# DC075B_JESD_OUTPUT.net
KiCad netlist of a schematic drawn in Altium Designer
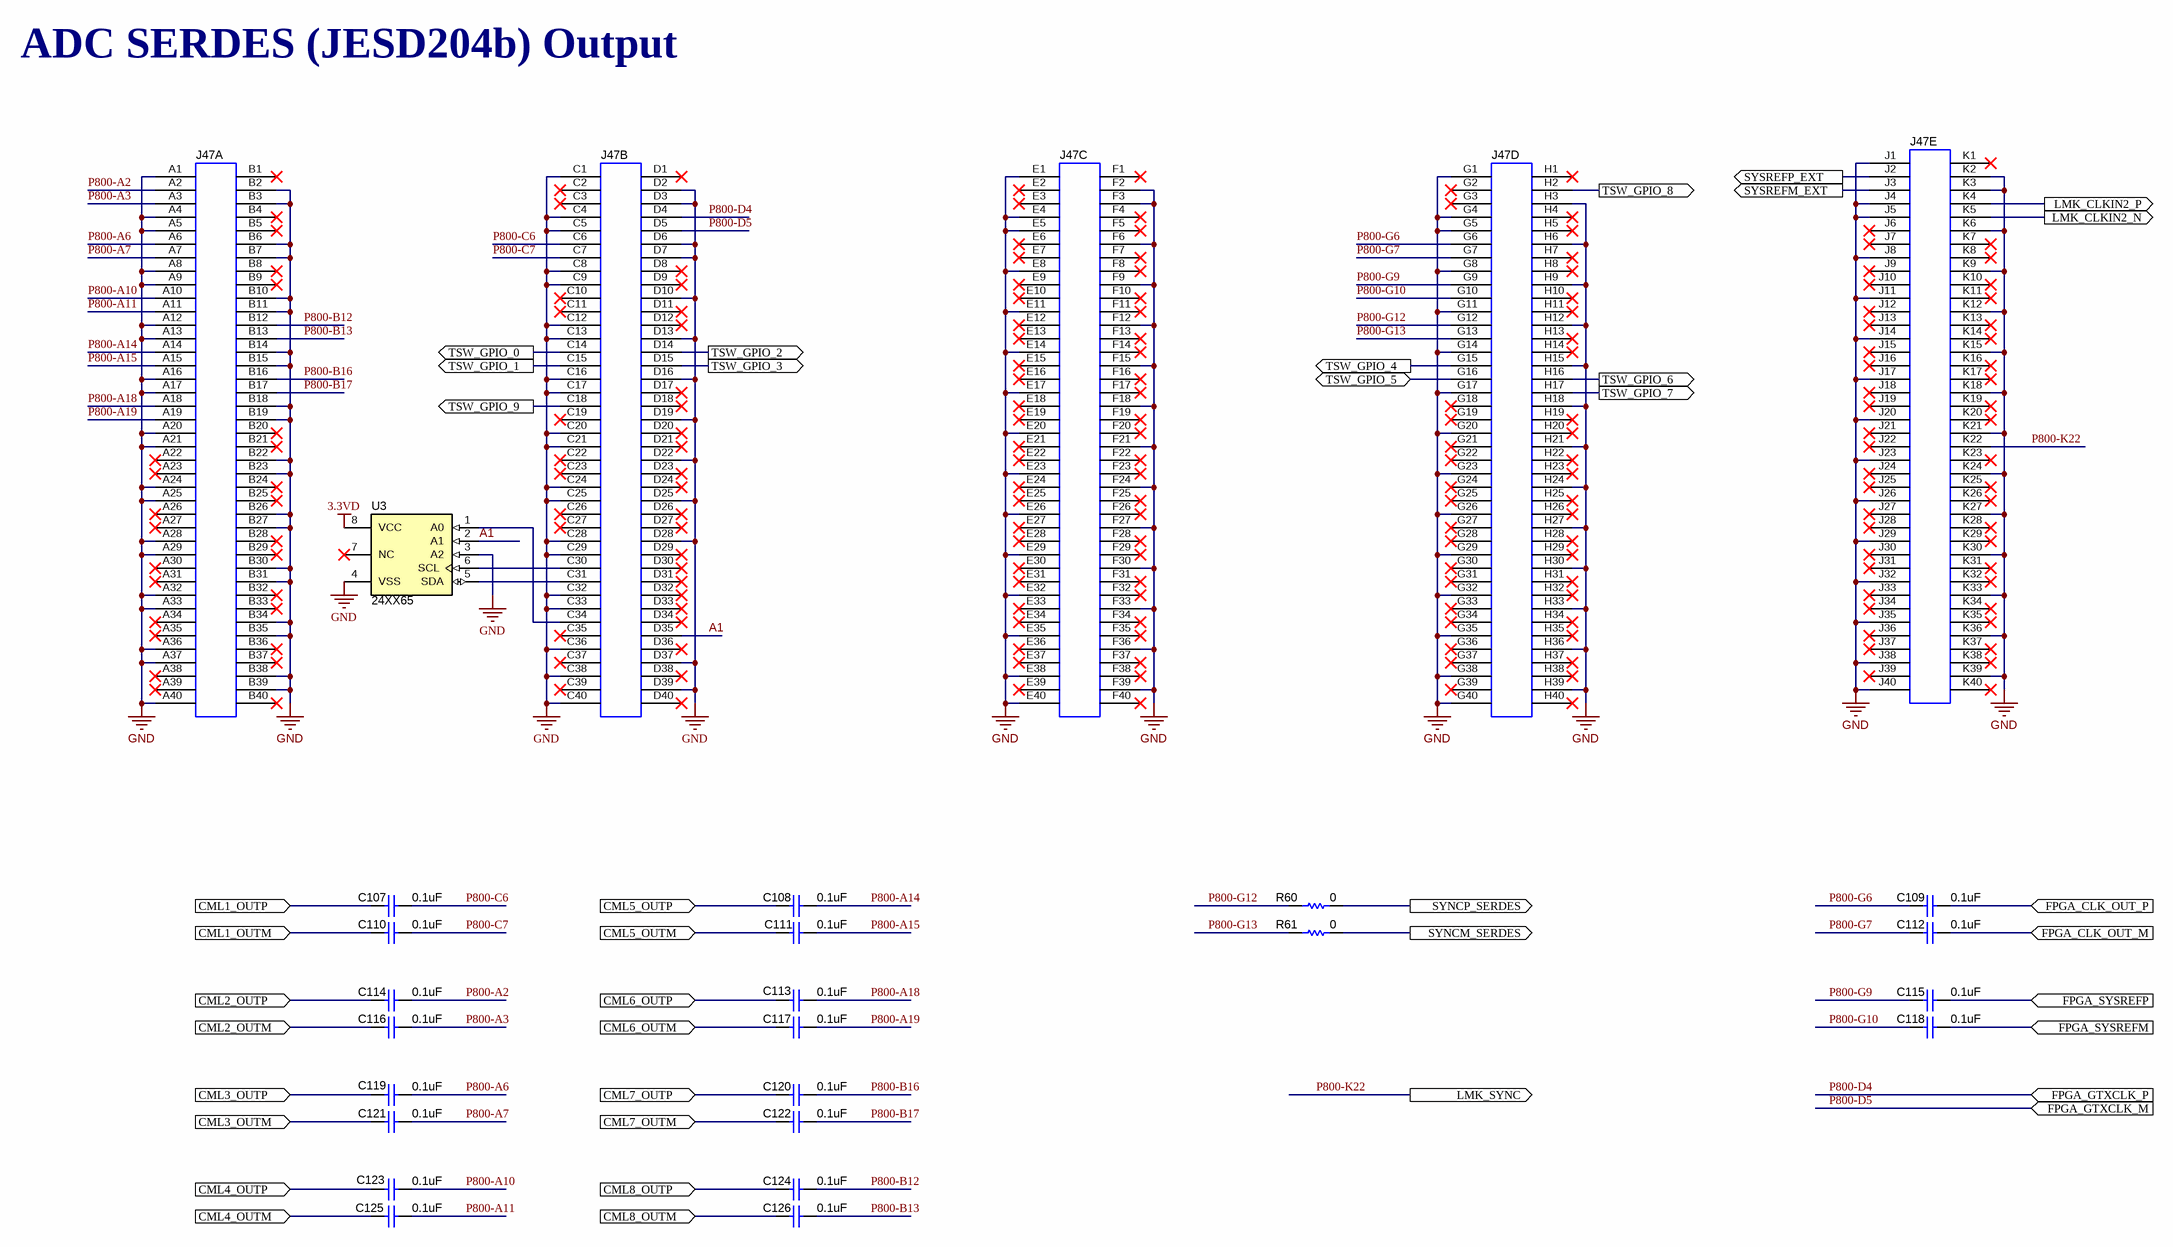
[diagram p0: DC075B_JESD_OUTPUT.SchDoc]

(export (version "E")
  (design (tool "Eeschema 10.0.6"))
  (components
    (comp (ref "C107")
      (value "0.1uF")
      (footprint "0402")
      (description "CAP, CERM, 0.1 uF, 16 V, +/- 10%, X7R, 0402")
      (fields
        (field (name "PARTNUMBER") "GRM155R71C104KA88D")
        (field (name "MANUFACTURER") "MuRata")
        (field (name "PUBLISHER") "Texas Instruments")
      )
      (libsource (lib "Altium Vault - TI") (part "Capacitor"))
    )
    (comp (ref "C108")
      (value "0.1uF")
      (footprint "0402")
      (description "CAP, CERM, 0.1 uF, 16 V, +/- 10%, X7R, 0402")
      (fields
        (field (name "PARTNUMBER") "GRM155R71C104KA88D")
        (field (name "MANUFACTURER") "MuRata")
        (field (name "PUBLISHER") "Texas Instruments")
      )
      (libsource (lib "Altium Vault - TI") (part "Capacitor"))
    )
    (comp (ref "C109")
      (value "0.1uF")
      (footprint "0402")
      (description "CAP, CERM, 0.1 uF, 16 V, +/- 10%, X7R, 0402")
      (fields
        (field (name "PARTNUMBER") "GRM155R71C104KA88D")
        (field (name "MANUFACTURER") "MuRata")
        (field (name "PUBLISHER") "Texas Instruments")
      )
      (libsource (lib "Altium Vault - TI") (part "Capacitor"))
    )
    (comp (ref "C110")
      (value "0.1uF")
      (footprint "0402")
      (description "CAP, CERM, 0.1 uF, 16 V, +/- 10%, X7R, 0402")
      (fields
        (field (name "PARTNUMBER") "GRM155R71C104KA88D")
        (field (name "MANUFACTURER") "MuRata")
        (field (name "PUBLISHER") "Texas Instruments")
      )
      (libsource (lib "Altium Vault - TI") (part "Capacitor"))
    )
    (comp (ref "C111")
      (value "0.1uF")
      (footprint "0402")
      (description "CAP, CERM, 0.1 uF, 16 V, +/- 10%, X7R, 0402")
      (fields
        (field (name "PARTNUMBER") "GRM155R71C104KA88D")
        (field (name "MANUFACTURER") "MuRata")
        (field (name "PUBLISHER") "Texas Instruments")
      )
      (libsource (lib "Altium Vault - TI") (part "Capacitor"))
    )
    (comp (ref "C112")
      (value "0.1uF")
      (footprint "0402")
      (description "CAP, CERM, 0.1 uF, 16 V, +/- 10%, X7R, 0402")
      (fields
        (field (name "PARTNUMBER") "GRM155R71C104KA88D")
        (field (name "MANUFACTURER") "MuRata")
        (field (name "PUBLISHER") "Texas Instruments")
      )
      (libsource (lib "Altium Vault - TI") (part "Capacitor"))
    )
    (comp (ref "C113")
      (value "0.1uF")
      (footprint "0402")
      (description "CAP, CERM, 0.1 uF, 16 V, +/- 10%, X7R, 0402")
      (fields
        (field (name "PARTNUMBER") "GRM155R71C104KA88D")
        (field (name "MANUFACTURER") "MuRata")
        (field (name "PUBLISHER") "Texas Instruments")
      )
      (libsource (lib "Altium Vault - TI") (part "Capacitor"))
    )
    (comp (ref "C114")
      (value "0.1uF")
      (footprint "0402")
      (description "CAP, CERM, 0.1 uF, 16 V, +/- 10%, X7R, 0402")
      (fields
        (field (name "PARTNUMBER") "GRM155R71C104KA88D")
        (field (name "MANUFACTURER") "MuRata")
        (field (name "PUBLISHER") "Texas Instruments")
      )
      (libsource (lib "Altium Vault - TI") (part "Capacitor"))
    )
    (comp (ref "C115")
      (value "0.1uF")
      (footprint "0402")
      (description "CAP, CERM, 0.1 uF, 16 V, +/- 10%, X7R, 0402")
      (fields
        (field (name "PARTNUMBER") "GRM155R71C104KA88D")
        (field (name "MANUFACTURER") "MuRata")
        (field (name "PUBLISHER") "Texas Instruments")
      )
      (libsource (lib "Altium Vault - TI") (part "Capacitor"))
    )
    (comp (ref "C116")
      (value "0.1uF")
      (footprint "0402")
      (description "CAP, CERM, 0.1 uF, 16 V, +/- 10%, X7R, 0402")
      (fields
        (field (name "PARTNUMBER") "GRM155R71C104KA88D")
        (field (name "MANUFACTURER") "MuRata")
        (field (name "PUBLISHER") "Texas Instruments")
      )
      (libsource (lib "Altium Vault - TI") (part "Capacitor"))
    )
    (comp (ref "C117")
      (value "0.1uF")
      (footprint "0402")
      (description "CAP, CERM, 0.1 uF, 16 V, +/- 10%, X7R, 0402")
      (fields
        (field (name "PARTNUMBER") "GRM155R71C104KA88D")
        (field (name "MANUFACTURER") "MuRata")
        (field (name "PUBLISHER") "Texas Instruments")
      )
      (libsource (lib "Altium Vault - TI") (part "Capacitor"))
    )
    (comp (ref "C118")
      (value "0.1uF")
      (footprint "0402")
      (description "CAP, CERM, 0.1 uF, 16 V, +/- 10%, X7R, 0402")
      (fields
        (field (name "PARTNUMBER") "GRM155R71C104KA88D")
        (field (name "MANUFACTURER") "MuRata")
        (field (name "PUBLISHER") "Texas Instruments")
      )
      (libsource (lib "Altium Vault - TI") (part "Capacitor"))
    )
    (comp (ref "C119")
      (value "0.1uF")
      (footprint "0402")
      (description "CAP, CERM, 0.1 uF, 16 V, +/- 10%, X7R, 0402")
      (fields
        (field (name "PARTNUMBER") "GRM155R71C104KA88D")
        (field (name "MANUFACTURER") "MuRata")
        (field (name "PUBLISHER") "Texas Instruments")
      )
      (libsource (lib "Altium Vault - TI") (part "Capacitor"))
    )
    (comp (ref "C120")
      (value "0.1uF")
      (footprint "0402")
      (description "CAP, CERM, 0.1 uF, 16 V, +/- 10%, X7R, 0402")
      (fields
        (field (name "PARTNUMBER") "GRM155R71C104KA88D")
        (field (name "MANUFACTURER") "MuRata")
        (field (name "PUBLISHER") "Texas Instruments")
      )
      (libsource (lib "Altium Vault - TI") (part "Capacitor"))
    )
    (comp (ref "C121")
      (value "0.1uF")
      (footprint "0402")
      (description "CAP, CERM, 0.1 uF, 16 V, +/- 10%, X7R, 0402")
      (fields
        (field (name "PARTNUMBER") "GRM155R71C104KA88D")
        (field (name "MANUFACTURER") "MuRata")
        (field (name "PUBLISHER") "Texas Instruments")
      )
      (libsource (lib "Altium Vault - TI") (part "Capacitor"))
    )
    (comp (ref "C122")
      (value "0.1uF")
      (footprint "0402")
      (description "CAP, CERM, 0.1 uF, 16 V, +/- 10%, X7R, 0402")
      (fields
        (field (name "PARTNUMBER") "GRM155R71C104KA88D")
        (field (name "MANUFACTURER") "MuRata")
        (field (name "PUBLISHER") "Texas Instruments")
      )
      (libsource (lib "Altium Vault - TI") (part "Capacitor"))
    )
    (comp (ref "C123")
      (value "0.1uF")
      (footprint "0402")
      (description "CAP, CERM, 0.1 uF, 16 V, +/- 10%, X7R, 0402")
      (fields
        (field (name "PARTNUMBER") "GRM155R71C104KA88D")
        (field (name "MANUFACTURER") "MuRata")
        (field (name "PUBLISHER") "Texas Instruments")
      )
      (libsource (lib "Altium Vault - TI") (part "Capacitor"))
    )
    (comp (ref "C124")
      (value "0.1uF")
      (footprint "0402")
      (description "CAP, CERM, 0.1 uF, 16 V, +/- 10%, X7R, 0402")
      (fields
        (field (name "PARTNUMBER") "GRM155R71C104KA88D")
        (field (name "MANUFACTURER") "MuRata")
        (field (name "PUBLISHER") "Texas Instruments")
      )
      (libsource (lib "Altium Vault - TI") (part "Capacitor"))
    )
    (comp (ref "C125")
      (value "0.1uF")
      (footprint "0402")
      (description "CAP, CERM, 0.1 uF, 16 V, +/- 10%, X7R, 0402")
      (fields
        (field (name "PARTNUMBER") "GRM155R71C104KA88D")
        (field (name "MANUFACTURER") "MuRata")
        (field (name "PUBLISHER") "Texas Instruments")
      )
      (libsource (lib "Altium Vault - TI") (part "Capacitor"))
    )
    (comp (ref "C126")
      (value "0.1uF")
      (footprint "0402")
      (description "CAP, CERM, 0.1 uF, 16 V, +/- 10%, X7R, 0402")
      (fields
        (field (name "PARTNUMBER") "GRM155R71C104KA88D")
        (field (name "MANUFACTURER") "MuRata")
        (field (name "PUBLISHER") "Texas Instruments")
      )
      (libsource (lib "Altium Vault - TI") (part "Capacitor"))
    )
    (comp (ref "J47")
      (value "SAMTEC_ASP-134602-01")
      (footprint "SAMTEC_ASP-134602-01")
      (description "Connector, Male, 1.27 mm, 40x4, SMD")
      (fields
        (field (name "PARTNUMBER") "ASP-134602-01")
        (field (name "MANUFACTURER") "Samtec")
        (field (name "PUBLISHER") "Texas Instruments")
      )
      (libsource (lib "Altium Vault - TI") (part "SAMTEC_ASP-134602-01"))
    )
    (comp (ref "R60")
      (value "0")
      (footprint "0402")
      (description "RES, 0, 5%, 0.063 W, AEC-Q200 Grade 0, 0402")
      (fields (field (name "MANUFACTURER") "Vishay-Dale") (field (name "PARTNUMBER") "CRCW04020000Z0ED"))
      (libsource (lib "Altium Vault - TI") (part "Resistor"))
    )
    (comp (ref "R61")
      (value "0")
      (footprint "0402")
      (description "RES, 0, 5%, 0.063 W, AEC-Q200 Grade 0, 0402")
      (fields (field (name "MANUFACTURER") "Vishay-Dale") (field (name "PARTNUMBER") "CRCW04020000Z0ED"))
      (libsource (lib "Altium Vault - TI") (part "Resistor"))
    )
    (comp (ref "U3")
      (value "24XX65")
      (footprint "SOIC127P800X216-8N")
      (description "64K I2C Smart Serial EEPROM, SOIC-8")
      (fields
        (field (name "PARTNUMBER") "24LC65-I/SM")
        (field (name "MANUFACTURER") "Microchip")
        (field (name "PUBLISHER") "Texas Instruments")
      )
      (libsource (lib "Altium Vault - TI") (part "24XX65"))
    )
  )
  (nets
    (net (code "1") (name "/A1") (class "Default")
      (node (ref "J47") (pin "D35") (pintype "passive"))
      (node (ref "U3") (pin "2") (pinfunction "A1_2") (pintype "input"))
    )
    (net (code "2") (name "/CML1_OUTM") (class "Default")
      (node (ref "C110") (pin "2") (pinfunction "2_2") (pintype "passive"))
    )
    (net (code "3") (name "/CML1_OUTP") (class "Default")
      (node (ref "C107") (pin "2") (pinfunction "2_2") (pintype "passive"))
    )
    (net (code "4") (name "/CML2_OUTM") (class "Default")
      (node (ref "C116") (pin "2") (pinfunction "2_2") (pintype "passive"))
    )
    (net (code "5") (name "/CML2_OUTP") (class "Default")
      (node (ref "C114") (pin "2") (pinfunction "2_2") (pintype "passive"))
    )
    (net (code "6") (name "/CML3_OUTM") (class "Default")
      (node (ref "C121") (pin "2") (pinfunction "2_2") (pintype "passive"))
    )
    (net (code "7") (name "/CML3_OUTP") (class "Default")
      (node (ref "C119") (pin "2") (pinfunction "2_2") (pintype "passive"))
    )
    (net (code "8") (name "/CML4_OUTM") (class "Default")
      (node (ref "C125") (pin "2") (pinfunction "2_2") (pintype "passive"))
    )
    (net (code "9") (name "/CML4_OUTP") (class "Default")
      (node (ref "C123") (pin "2") (pinfunction "2_2") (pintype "passive"))
    )
    (net (code "10") (name "/CML5_OUTM") (class "Default")
      (node (ref "C111") (pin "2") (pinfunction "2_2") (pintype "passive"))
    )
    (net (code "11") (name "/CML5_OUTP") (class "Default")
      (node (ref "C108") (pin "2") (pinfunction "2_2") (pintype "passive"))
    )
    (net (code "12") (name "/CML6_OUTM") (class "Default")
      (node (ref "C117") (pin "2") (pinfunction "2_2") (pintype "passive"))
    )
    (net (code "13") (name "/CML6_OUTP") (class "Default")
      (node (ref "C113") (pin "2") (pinfunction "2_2") (pintype "passive"))
    )
    (net (code "14") (name "/CML7_OUTM") (class "Default")
      (node (ref "C122") (pin "2") (pinfunction "2_2") (pintype "passive"))
    )
    (net (code "15") (name "/CML7_OUTP") (class "Default")
      (node (ref "C120") (pin "2") (pinfunction "2_2") (pintype "passive"))
    )
    (net (code "16") (name "/CML8_OUTM") (class "Default")
      (node (ref "C126") (pin "2") (pinfunction "2_2") (pintype "passive"))
    )
    (net (code "17") (name "/CML8_OUTP") (class "Default")
      (node (ref "C124") (pin "2") (pinfunction "2_2") (pintype "passive"))
    )
    (net (code "18") (name "/FPGA_CLK_OUT_M") (class "Default")
      (node (ref "C112") (pin "1") (pinfunction "1_1") (pintype "passive"))
    )
    (net (code "19") (name "/FPGA_CLK_OUT_P") (class "Default")
      (node (ref "C109") (pin "1") (pinfunction "1_1") (pintype "passive"))
    )
    (net (code "20") (name "/FPGA_SYSREFM") (class "Default")
      (node (ref "C118") (pin "1") (pinfunction "1_1") (pintype "passive"))
    )
    (net (code "21") (name "/FPGA_SYSREFP") (class "Default")
      (node (ref "C115") (pin "1") (pinfunction "1_1") (pintype "passive"))
    )
    (net (code "22") (name "/LMK_CLKIN2_N") (class "Default")
      (node (ref "J47") (pin "K5") (pintype "passive"))
    )
    (net (code "23") (name "/LMK_CLKIN2_P") (class "Default")
      (node (ref "J47") (pin "K4") (pintype "passive"))
    )
    (net (code "24") (name "/P800-A2") (class "Default")
      (node (ref "C114") (pin "1") (pinfunction "1_1") (pintype "passive"))
      (node (ref "J47") (pin "A2") (pintype "passive"))
    )
    (net (code "25") (name "/P800-A3") (class "Default")
      (node (ref "C116") (pin "1") (pinfunction "1_1") (pintype "passive"))
      (node (ref "J47") (pin "A3") (pintype "passive"))
    )
    (net (code "26") (name "/P800-A6") (class "Default")
      (node (ref "C119") (pin "1") (pinfunction "1_1") (pintype "passive"))
      (node (ref "J47") (pin "A6") (pintype "passive"))
    )
    (net (code "27") (name "/P800-A7") (class "Default")
      (node (ref "C121") (pin "1") (pinfunction "1_1") (pintype "passive"))
      (node (ref "J47") (pin "A7") (pintype "passive"))
    )
    (net (code "28") (name "/P800-A10") (class "Default")
      (node (ref "C123") (pin "1") (pinfunction "1_1") (pintype "passive"))
      (node (ref "J47") (pin "A10") (pintype "passive"))
    )
    (net (code "29") (name "/P800-A11") (class "Default")
      (node (ref "C125") (pin "1") (pinfunction "1_1") (pintype "passive"))
      (node (ref "J47") (pin "A11") (pintype "passive"))
    )
    (net (code "30") (name "/P800-A14") (class "Default")
      (node (ref "C108") (pin "1") (pinfunction "1_1") (pintype "passive"))
      (node (ref "J47") (pin "A14") (pintype "passive"))
    )
    (net (code "31") (name "/P800-A15") (class "Default")
      (node (ref "C111") (pin "1") (pinfunction "1_1") (pintype "passive"))
      (node (ref "J47") (pin "A15") (pintype "passive"))
    )
    (net (code "32") (name "/P800-A18") (class "Default")
      (node (ref "C113") (pin "1") (pinfunction "1_1") (pintype "passive"))
      (node (ref "J47") (pin "A18") (pintype "passive"))
    )
    (net (code "33") (name "/P800-A19") (class "Default")
      (node (ref "C117") (pin "1") (pinfunction "1_1") (pintype "passive"))
      (node (ref "J47") (pin "A19") (pintype "passive"))
    )
    (net (code "34") (name "/P800-B12") (class "Default")
      (node (ref "C124") (pin "1") (pinfunction "1_1") (pintype "passive"))
      (node (ref "J47") (pin "B12") (pintype "passive"))
    )
    (net (code "35") (name "/P800-B13") (class "Default")
      (node (ref "C126") (pin "1") (pinfunction "1_1") (pintype "passive"))
      (node (ref "J47") (pin "B13") (pintype "passive"))
    )
    (net (code "36") (name "/P800-B16") (class "Default")
      (node (ref "C120") (pin "1") (pinfunction "1_1") (pintype "passive"))
      (node (ref "J47") (pin "B16") (pintype "passive"))
    )
    (net (code "37") (name "/P800-B17") (class "Default")
      (node (ref "C122") (pin "1") (pinfunction "1_1") (pintype "passive"))
      (node (ref "J47") (pin "B17") (pintype "passive"))
    )
    (net (code "38") (name "/P800-C6") (class "Default")
      (node (ref "C107") (pin "1") (pinfunction "1_1") (pintype "passive"))
      (node (ref "J47") (pin "C6") (pintype "passive"))
    )
    (net (code "39") (name "/P800-C7") (class "Default")
      (node (ref "C110") (pin "1") (pinfunction "1_1") (pintype "passive"))
      (node (ref "J47") (pin "C7") (pintype "passive"))
    )
    (net (code "40") (name "/P800-D4") (class "Default") (node (ref "J47") (pin "D4") (pintype "passive")))
    (net (code "41") (name "/P800-D5") (class "Default") (node (ref "J47") (pin "D5") (pintype "passive")))
    (net (code "42") (name "/P800-G6") (class "Default")
      (node (ref "C109") (pin "2") (pinfunction "2_2") (pintype "passive"))
      (node (ref "J47") (pin "G6") (pintype "passive"))
    )
    (net (code "43") (name "/P800-G7") (class "Default")
      (node (ref "C112") (pin "2") (pinfunction "2_2") (pintype "passive"))
      (node (ref "J47") (pin "G7") (pintype "passive"))
    )
    (net (code "44") (name "/P800-G9") (class "Default")
      (node (ref "C115") (pin "2") (pinfunction "2_2") (pintype "passive"))
      (node (ref "J47") (pin "G9") (pintype "passive"))
    )
    (net (code "45") (name "/P800-G10") (class "Default")
      (node (ref "C118") (pin "2") (pinfunction "2_2") (pintype "passive"))
      (node (ref "J47") (pin "G10") (pintype "passive"))
    )
    (net (code "46") (name "/P800-G12") (class "Default")
      (node (ref "J47") (pin "G12") (pintype "passive"))
      (node (ref "R60") (pin "1") (pinfunction "1_1") (pintype "passive"))
    )
    (net (code "47") (name "/P800-G13") (class "Default")
      (node (ref "J47") (pin "G13") (pintype "passive"))
      (node (ref "R61") (pin "1") (pinfunction "1_1") (pintype "passive"))
    )
    (net (code "48") (name "/P800-K22") (class "Default") (node (ref "J47") (pin "K22") (pintype "passive")))
    (net (code "49") (name "/SYNCM_SERDES") (class "Default")
      (node (ref "R61") (pin "2") (pinfunction "2_2") (pintype "passive"))
    )
    (net (code "50") (name "/SYNCP_SERDES") (class "Default")
      (node (ref "R60") (pin "2") (pinfunction "2_2") (pintype "passive"))
    )
    (net (code "51") (name "/SYSREFM_EXT") (class "Default")
      (node (ref "J47") (pin "J3") (pintype "passive"))
    )
    (net (code "52") (name "/SYSREFP_EXT") (class "Default")
      (node (ref "J47") (pin "J2") (pintype "passive"))
    )
    (net (code "53") (name "/TSW_GPIO_0") (class "Default")
      (node (ref "J47") (pin "C14") (pintype "passive"))
    )
    (net (code "54") (name "/TSW_GPIO_1") (class "Default")
      (node (ref "J47") (pin "C15") (pintype "passive"))
    )
    (net (code "55") (name "/TSW_GPIO_2") (class "Default")
      (node (ref "J47") (pin "D14") (pintype "passive"))
    )
    (net (code "56") (name "/TSW_GPIO_3") (class "Default")
      (node (ref "J47") (pin "D15") (pintype "passive"))
    )
    (net (code "57") (name "/TSW_GPIO_4") (class "Default")
      (node (ref "J47") (pin "G15") (pintype "passive"))
    )
    (net (code "58") (name "/TSW_GPIO_5") (class "Default")
      (node (ref "J47") (pin "G16") (pintype "passive"))
    )
    (net (code "59") (name "/TSW_GPIO_6") (class "Default")
      (node (ref "J47") (pin "H16") (pintype "passive"))
    )
    (net (code "60") (name "/TSW_GPIO_7") (class "Default")
      (node (ref "J47") (pin "H17") (pintype "passive"))
    )
    (net (code "61") (name "/TSW_GPIO_8") (class "Default") (node (ref "J47") (pin "H2") (pintype "passive")))
    (net (code "62") (name "/TSW_GPIO_9") (class "Default")
      (node (ref "J47") (pin "C18") (pintype "passive"))
    )
    (net (code "63") (name "3.3VD") (class "Default")
      (node (ref "U3") (pin "8") (pinfunction "VCC_8") (pintype "power_in"))
    )
    (net (code "64") (name "GND") (class "Default")
      (node (ref "J47") (pin "A1") (pintype "passive"))
      (node (ref "J47") (pin "A12") (pintype "passive"))
      (node (ref "J47") (pin "A13") (pintype "passive"))
      (node (ref "J47") (pin "A16") (pintype "passive"))
      (node (ref "J47") (pin "A17") (pintype "passive"))
      (node (ref "J47") (pin "A20") (pintype "passive"))
      (node (ref "J47") (pin "A21") (pintype "passive"))
      (node (ref "J47") (pin "A24") (pintype "passive"))
      (node (ref "J47") (pin "A25") (pintype "passive"))
      (node (ref "J47") (pin "A28") (pintype "passive"))
      (node (ref "J47") (pin "A29") (pintype "passive"))
      (node (ref "J47") (pin "A32") (pintype "passive"))
      (node (ref "J47") (pin "A33") (pintype "passive"))
      (node (ref "J47") (pin "A36") (pintype "passive"))
      (node (ref "J47") (pin "A37") (pintype "passive"))
      (node (ref "J47") (pin "A4") (pintype "passive"))
      (node (ref "J47") (pin "A40") (pintype "passive"))
      (node (ref "J47") (pin "A5") (pintype "passive"))
      (node (ref "J47") (pin "A8") (pintype "passive"))
      (node (ref "J47") (pin "A9") (pintype "passive"))
      (node (ref "J47") (pin "B10") (pintype "passive"))
      (node (ref "J47") (pin "B11") (pintype "passive"))
      (node (ref "J47") (pin "B14") (pintype "passive"))
      (node (ref "J47") (pin "B15") (pintype "passive"))
      (node (ref "J47") (pin "B18") (pintype "passive"))
      (node (ref "J47") (pin "B19") (pintype "passive"))
      (node (ref "J47") (pin "B2") (pintype "passive"))
      (node (ref "J47") (pin "B22") (pintype "passive"))
      (node (ref "J47") (pin "B23") (pintype "passive"))
      (node (ref "J47") (pin "B26") (pintype "passive"))
      (node (ref "J47") (pin "B27") (pintype "passive"))
      (node (ref "J47") (pin "B3") (pintype "passive"))
      (node (ref "J47") (pin "B30") (pintype "passive"))
      (node (ref "J47") (pin "B31") (pintype "passive"))
      (node (ref "J47") (pin "B34") (pintype "passive"))
      (node (ref "J47") (pin "B35") (pintype "passive"))
      (node (ref "J47") (pin "B38") (pintype "passive"))
      (node (ref "J47") (pin "B39") (pintype "passive"))
      (node (ref "J47") (pin "B6") (pintype "passive"))
      (node (ref "J47") (pin "B7") (pintype "passive"))
      (node (ref "J47") (pin "C1") (pintype "passive"))
      (node (ref "J47") (pin "C12") (pintype "passive"))
      (node (ref "J47") (pin "C13") (pintype "passive"))
      (node (ref "J47") (pin "C16") (pintype "passive"))
      (node (ref "J47") (pin "C17") (pintype "passive"))
      (node (ref "J47") (pin "C20") (pintype "passive"))
      (node (ref "J47") (pin "C21") (pintype "passive"))
      (node (ref "J47") (pin "C24") (pintype "passive"))
      (node (ref "J47") (pin "C25") (pintype "passive"))
      (node (ref "J47") (pin "C28") (pintype "passive"))
      (node (ref "J47") (pin "C29") (pintype "passive"))
      (node (ref "J47") (pin "C32") (pintype "passive"))
      (node (ref "J47") (pin "C33") (pintype "passive"))
      (node (ref "J47") (pin "C36") (pintype "passive"))
      (node (ref "J47") (pin "C38") (pintype "passive"))
      (node (ref "J47") (pin "C4") (pintype "passive"))
      (node (ref "J47") (pin "C40") (pintype "passive"))
      (node (ref "J47") (pin "C5") (pintype "passive"))
      (node (ref "J47") (pin "C8") (pintype "passive"))
      (node (ref "J47") (pin "C9") (pintype "passive"))
      (node (ref "J47") (pin "D10") (pintype "passive"))
      (node (ref "J47") (pin "D13") (pintype "passive"))
      (node (ref "J47") (pin "D16") (pintype "passive"))
      (node (ref "J47") (pin "D19") (pintype "passive"))
      (node (ref "J47") (pin "D2") (pintype "passive"))
      (node (ref "J47") (pin "D22") (pintype "passive"))
      (node (ref "J47") (pin "D25") (pintype "passive"))
      (node (ref "J47") (pin "D28") (pintype "passive"))
      (node (ref "J47") (pin "D3") (pintype "passive"))
      (node (ref "J47") (pin "D37") (pintype "passive"))
      (node (ref "J47") (pin "D39") (pintype "passive"))
      (node (ref "J47") (pin "D6") (pintype "passive"))
      (node (ref "J47") (pin "D7") (pintype "passive"))
      (node (ref "J47") (pin "E1") (pintype "passive"))
      (node (ref "J47") (pin "E11") (pintype "passive"))
      (node (ref "J47") (pin "E14") (pintype "passive"))
      (node (ref "J47") (pin "E17") (pintype "passive"))
      (node (ref "J47") (pin "E20") (pintype "passive"))
      (node (ref "J47") (pin "E23") (pintype "passive"))
      (node (ref "J47") (pin "E26") (pintype "passive"))
      (node (ref "J47") (pin "E29") (pintype "passive"))
      (node (ref "J47") (pin "E32") (pintype "passive"))
      (node (ref "J47") (pin "E35") (pintype "passive"))
      (node (ref "J47") (pin "E38") (pintype "passive"))
      (node (ref "J47") (pin "E4") (pintype "passive"))
      (node (ref "J47") (pin "E40") (pintype "passive"))
      (node (ref "J47") (pin "E5") (pintype "passive"))
      (node (ref "J47") (pin "E8") (pintype "passive"))
      (node (ref "J47") (pin "F12") (pintype "passive"))
      (node (ref "J47") (pin "F15") (pintype "passive"))
      (node (ref "J47") (pin "F18") (pintype "passive"))
      (node (ref "J47") (pin "F2") (pintype "passive"))
      (node (ref "J47") (pin "F21") (pintype "passive"))
      (node (ref "J47") (pin "F24") (pintype "passive"))
      (node (ref "J47") (pin "F27") (pintype "passive"))
      (node (ref "J47") (pin "F3") (pintype "passive"))
      (node (ref "J47") (pin "F30") (pintype "passive"))
      (node (ref "J47") (pin "F33") (pintype "passive"))
      (node (ref "J47") (pin "F36") (pintype "passive"))
      (node (ref "J47") (pin "F39") (pintype "passive"))
      (node (ref "J47") (pin "F6") (pintype "passive"))
      (node (ref "J47") (pin "F9") (pintype "passive"))
      (node (ref "J47") (pin "G1") (pintype "passive"))
      (node (ref "J47") (pin "G11") (pintype "passive"))
      (node (ref "J47") (pin "G14") (pintype "passive"))
      (node (ref "J47") (pin "G17") (pintype "passive"))
      (node (ref "J47") (pin "G20") (pintype "passive"))
      (node (ref "J47") (pin "G23") (pintype "passive"))
      (node (ref "J47") (pin "G26") (pintype "passive"))
      (node (ref "J47") (pin "G29") (pintype "passive"))
      (node (ref "J47") (pin "G32") (pintype "passive"))
      (node (ref "J47") (pin "G35") (pintype "passive"))
      (node (ref "J47") (pin "G38") (pintype "passive"))
      (node (ref "J47") (pin "G4") (pintype "passive"))
      (node (ref "J47") (pin "G40") (pintype "passive"))
      (node (ref "J47") (pin "G5") (pintype "passive"))
      (node (ref "J47") (pin "G8") (pintype "passive"))
      (node (ref "J47") (pin "H12") (pintype "passive"))
      (node (ref "J47") (pin "H15") (pintype "passive"))
      (node (ref "J47") (pin "H18") (pintype "passive"))
      (node (ref "J47") (pin "H21") (pintype "passive"))
      (node (ref "J47") (pin "H24") (pintype "passive"))
      (node (ref "J47") (pin "H27") (pintype "passive"))
      (node (ref "J47") (pin "H3") (pintype "passive"))
      (node (ref "J47") (pin "H30") (pintype "passive"))
      (node (ref "J47") (pin "H33") (pintype "passive"))
      (node (ref "J47") (pin "H36") (pintype "passive"))
      (node (ref "J47") (pin "H39") (pintype "passive"))
      (node (ref "J47") (pin "H6") (pintype "passive"))
      (node (ref "J47") (pin "H9") (pintype "passive"))
      (node (ref "J47") (pin "J1") (pintype "passive"))
      (node (ref "J47") (pin "J11") (pintype "passive"))
      (node (ref "J47") (pin "J14") (pintype "passive"))
      (node (ref "J47") (pin "J17") (pintype "passive"))
      (node (ref "J47") (pin "J20") (pintype "passive"))
      (node (ref "J47") (pin "J23") (pintype "passive"))
      (node (ref "J47") (pin "J26") (pintype "passive"))
      (node (ref "J47") (pin "J29") (pintype "passive"))
      (node (ref "J47") (pin "J32") (pintype "passive"))
      (node (ref "J47") (pin "J35") (pintype "passive"))
      (node (ref "J47") (pin "J38") (pintype "passive"))
      (node (ref "J47") (pin "J4") (pintype "passive"))
      (node (ref "J47") (pin "J40") (pintype "passive"))
      (node (ref "J47") (pin "J5") (pintype "passive"))
      (node (ref "J47") (pin "J8") (pintype "passive"))
      (node (ref "J47") (pin "K12") (pintype "passive"))
      (node (ref "J47") (pin "K15") (pintype "passive"))
      (node (ref "J47") (pin "K18") (pintype "passive"))
      (node (ref "J47") (pin "K2") (pintype "passive"))
      (node (ref "J47") (pin "K21") (pintype "passive"))
      (node (ref "J47") (pin "K24") (pintype "passive"))
      (node (ref "J47") (pin "K27") (pintype "passive"))
      (node (ref "J47") (pin "K3") (pintype "passive"))
      (node (ref "J47") (pin "K30") (pintype "passive"))
      (node (ref "J47") (pin "K33") (pintype "passive"))
      (node (ref "J47") (pin "K36") (pintype "passive"))
      (node (ref "J47") (pin "K39") (pintype "passive"))
      (node (ref "J47") (pin "K6") (pintype "passive"))
      (node (ref "J47") (pin "K9") (pintype "passive"))
      (node (ref "U3") (pin "3") (pinfunction "A2_3") (pintype "input"))
      (node (ref "U3") (pin "4") (pinfunction "VSS_4") (pintype "power_in"))
    )
    (net (code "65") (name "Net-(U3-A0)") (class "Default")
      (node (ref "J47") (pin "C34") (pintype "passive"))
      (node (ref "U3") (pin "1") (pinfunction "A0_1") (pintype "input"))
    )
    (net (code "66") (name "Net-(U3-SCL)") (class "Default")
      (node (ref "J47") (pin "C30") (pintype "passive"))
      (node (ref "U3") (pin "6") (pinfunction "SCL_6") (pintype "input"))
    )
    (net (code "67") (name "Net-(U3-SDA)") (class "Default")
      (node (ref "J47") (pin "C31") (pintype "passive"))
      (node (ref "U3") (pin "5") (pinfunction "SDA_5") (pintype "bidirectional"))
    )
    (net (code "68") (name "unconnected-(J47-PadA22)") (class "Default")
      (node (ref "J47") (pin "A22") (pintype "passive+no_connect"))
    )
    (net (code "69") (name "unconnected-(J47-PadA23)") (class "Default")
      (node (ref "J47") (pin "A23") (pintype "passive+no_connect"))
    )
    (net (code "70") (name "unconnected-(J47-PadA26)") (class "Default")
      (node (ref "J47") (pin "A26") (pintype "passive+no_connect"))
    )
    (net (code "71") (name "unconnected-(J47-PadA27)") (class "Default")
      (node (ref "J47") (pin "A27") (pintype "passive+no_connect"))
    )
    (net (code "72") (name "unconnected-(J47-PadA30)") (class "Default")
      (node (ref "J47") (pin "A30") (pintype "passive+no_connect"))
    )
    (net (code "73") (name "unconnected-(J47-PadA31)") (class "Default")
      (node (ref "J47") (pin "A31") (pintype "passive+no_connect"))
    )
    (net (code "74") (name "unconnected-(J47-PadA34)") (class "Default")
      (node (ref "J47") (pin "A34") (pintype "passive+no_connect"))
    )
    (net (code "75") (name "unconnected-(J47-PadA35)") (class "Default")
      (node (ref "J47") (pin "A35") (pintype "passive+no_connect"))
    )
    (net (code "76") (name "unconnected-(J47-PadA38)") (class "Default")
      (node (ref "J47") (pin "A38") (pintype "passive+no_connect"))
    )
    (net (code "77") (name "unconnected-(J47-PadA39)") (class "Default")
      (node (ref "J47") (pin "A39") (pintype "passive+no_connect"))
    )
    (net (code "78") (name "unconnected-(J47-PadB1)") (class "Default")
      (node (ref "J47") (pin "B1") (pintype "passive+no_connect"))
    )
    (net (code "79") (name "unconnected-(J47-PadB4)") (class "Default")
      (node (ref "J47") (pin "B4") (pintype "passive+no_connect"))
    )
    (net (code "80") (name "unconnected-(J47-PadB5)") (class "Default")
      (node (ref "J47") (pin "B5") (pintype "passive+no_connect"))
    )
    (net (code "81") (name "unconnected-(J47-PadB8)") (class "Default")
      (node (ref "J47") (pin "B8") (pintype "passive+no_connect"))
    )
    (net (code "82") (name "unconnected-(J47-PadB9)") (class "Default")
      (node (ref "J47") (pin "B9") (pintype "passive+no_connect"))
    )
    (net (code "83") (name "unconnected-(J47-PadB20)") (class "Default")
      (node (ref "J47") (pin "B20") (pintype "passive+no_connect"))
    )
    (net (code "84") (name "unconnected-(J47-PadB21)") (class "Default")
      (node (ref "J47") (pin "B21") (pintype "passive+no_connect"))
    )
    (net (code "85") (name "unconnected-(J47-PadB24)") (class "Default")
      (node (ref "J47") (pin "B24") (pintype "passive+no_connect"))
    )
    (net (code "86") (name "unconnected-(J47-PadB25)") (class "Default")
      (node (ref "J47") (pin "B25") (pintype "passive+no_connect"))
    )
    (net (code "87") (name "unconnected-(J47-PadB28)") (class "Default")
      (node (ref "J47") (pin "B28") (pintype "passive+no_connect"))
    )
    (net (code "88") (name "unconnected-(J47-PadB29)") (class "Default")
      (node (ref "J47") (pin "B29") (pintype "passive+no_connect"))
    )
    (net (code "89") (name "unconnected-(J47-PadB32)") (class "Default")
      (node (ref "J47") (pin "B32") (pintype "passive+no_connect"))
    )
    (net (code "90") (name "unconnected-(J47-PadB33)") (class "Default")
      (node (ref "J47") (pin "B33") (pintype "passive+no_connect"))
    )
    (net (code "91") (name "unconnected-(J47-PadB36)") (class "Default")
      (node (ref "J47") (pin "B36") (pintype "passive+no_connect"))
    )
    (net (code "92") (name "unconnected-(J47-PadB37)") (class "Default")
      (node (ref "J47") (pin "B37") (pintype "passive+no_connect"))
    )
    (net (code "93") (name "unconnected-(J47-PadB40)") (class "Default")
      (node (ref "J47") (pin "B40") (pintype "passive+no_connect"))
    )
    (net (code "94") (name "unconnected-(J47-PadC2)") (class "Default")
      (node (ref "J47") (pin "C2") (pintype "passive+no_connect"))
    )
    (net (code "95") (name "unconnected-(J47-PadC3)") (class "Default")
      (node (ref "J47") (pin "C3") (pintype "passive+no_connect"))
    )
    (net (code "96") (name "unconnected-(J47-PadC10)") (class "Default")
      (node (ref "J47") (pin "C10") (pintype "passive+no_connect"))
    )
    (net (code "97") (name "unconnected-(J47-PadC11)") (class "Default")
      (node (ref "J47") (pin "C11") (pintype "passive+no_connect"))
    )
    (net (code "98") (name "unconnected-(J47-PadC19)") (class "Default")
      (node (ref "J47") (pin "C19") (pintype "passive+no_connect"))
    )
    (net (code "99") (name "unconnected-(J47-PadC22)") (class "Default")
      (node (ref "J47") (pin "C22") (pintype "passive+no_connect"))
    )
    (net (code "100") (name "unconnected-(J47-PadC23)") (class "Default")
      (node (ref "J47") (pin "C23") (pintype "passive+no_connect"))
    )
    (net (code "101") (name "unconnected-(J47-PadC26)") (class "Default")
      (node (ref "J47") (pin "C26") (pintype "passive+no_connect"))
    )
    (net (code "102") (name "unconnected-(J47-PadC27)") (class "Default")
      (node (ref "J47") (pin "C27") (pintype "passive+no_connect"))
    )
    (net (code "103") (name "unconnected-(J47-PadC35)") (class "Default")
      (node (ref "J47") (pin "C35") (pintype "passive+no_connect"))
    )
    (net (code "104") (name "unconnected-(J47-PadC37)") (class "Default")
      (node (ref "J47") (pin "C37") (pintype "passive+no_connect"))
    )
    (net (code "105") (name "unconnected-(J47-PadC39)") (class "Default")
      (node (ref "J47") (pin "C39") (pintype "passive+no_connect"))
    )
    (net (code "106") (name "unconnected-(J47-PadD1)") (class "Default")
      (node (ref "J47") (pin "D1") (pintype "passive+no_connect"))
    )
    (net (code "107") (name "unconnected-(J47-PadD8)") (class "Default")
      (node (ref "J47") (pin "D8") (pintype "passive+no_connect"))
    )
    (net (code "108") (name "unconnected-(J47-PadD9)") (class "Default")
      (node (ref "J47") (pin "D9") (pintype "passive+no_connect"))
    )
    (net (code "109") (name "unconnected-(J47-PadD11)") (class "Default")
      (node (ref "J47") (pin "D11") (pintype "passive+no_connect"))
    )
    (net (code "110") (name "unconnected-(J47-PadD12)") (class "Default")
      (node (ref "J47") (pin "D12") (pintype "passive+no_connect"))
    )
    (net (code "111") (name "unconnected-(J47-PadD17)") (class "Default")
      (node (ref "J47") (pin "D17") (pintype "passive+no_connect"))
    )
    (net (code "112") (name "unconnected-(J47-PadD18)") (class "Default")
      (node (ref "J47") (pin "D18") (pintype "passive+no_connect"))
    )
    (net (code "113") (name "unconnected-(J47-PadD20)") (class "Default")
      (node (ref "J47") (pin "D20") (pintype "passive+no_connect"))
    )
    (net (code "114") (name "unconnected-(J47-PadD21)") (class "Default")
      (node (ref "J47") (pin "D21") (pintype "passive+no_connect"))
    )
    (net (code "115") (name "unconnected-(J47-PadD23)") (class "Default")
      (node (ref "J47") (pin "D23") (pintype "passive+no_connect"))
    )
    (net (code "116") (name "unconnected-(J47-PadD24)") (class "Default")
      (node (ref "J47") (pin "D24") (pintype "passive+no_connect"))
    )
    (net (code "117") (name "unconnected-(J47-PadD26)") (class "Default")
      (node (ref "J47") (pin "D26") (pintype "passive+no_connect"))
    )
    (net (code "118") (name "unconnected-(J47-PadD27)") (class "Default")
      (node (ref "J47") (pin "D27") (pintype "passive+no_connect"))
    )
    (net (code "119") (name "unconnected-(J47-PadD29)") (class "Default")
      (node (ref "J47") (pin "D29") (pintype "passive+no_connect"))
    )
    (net (code "120") (name "unconnected-(J47-PadD30)") (class "Default")
      (node (ref "J47") (pin "D30") (pintype "passive+no_connect"))
    )
    (net (code "121") (name "unconnected-(J47-PadD31)") (class "Default")
      (node (ref "J47") (pin "D31") (pintype "passive+no_connect"))
    )
    (net (code "122") (name "unconnected-(J47-PadD32)") (class "Default")
      (node (ref "J47") (pin "D32") (pintype "passive+no_connect"))
    )
    (net (code "123") (name "unconnected-(J47-PadD33)") (class "Default")
      (node (ref "J47") (pin "D33") (pintype "passive+no_connect"))
    )
    (net (code "124") (name "unconnected-(J47-PadD34)") (class "Default")
      (node (ref "J47") (pin "D34") (pintype "passive+no_connect"))
    )
    (net (code "125") (name "unconnected-(J47-PadD36)") (class "Default")
      (node (ref "J47") (pin "D36") (pintype "passive+no_connect"))
    )
    (net (code "126") (name "unconnected-(J47-PadD38)") (class "Default")
      (node (ref "J47") (pin "D38") (pintype "passive+no_connect"))
    )
    (net (code "127") (name "unconnected-(J47-PadD40)") (class "Default")
      (node (ref "J47") (pin "D40") (pintype "passive+no_connect"))
    )
    (net (code "128") (name "unconnected-(J47-PadE2)") (class "Default")
      (node (ref "J47") (pin "E2") (pintype "passive+no_connect"))
    )
    (net (code "129") (name "unconnected-(J47-PadE3)") (class "Default")
      (node (ref "J47") (pin "E3") (pintype "passive+no_connect"))
    )
    (net (code "130") (name "unconnected-(J47-PadE6)") (class "Default")
      (node (ref "J47") (pin "E6") (pintype "passive+no_connect"))
    )
    (net (code "131") (name "unconnected-(J47-PadE7)") (class "Default")
      (node (ref "J47") (pin "E7") (pintype "passive+no_connect"))
    )
    (net (code "132") (name "unconnected-(J47-PadE9)") (class "Default")
      (node (ref "J47") (pin "E9") (pintype "passive+no_connect"))
    )
    (net (code "133") (name "unconnected-(J47-PadE10)") (class "Default")
      (node (ref "J47") (pin "E10") (pintype "passive+no_connect"))
    )
    (net (code "134") (name "unconnected-(J47-PadE12)") (class "Default")
      (node (ref "J47") (pin "E12") (pintype "passive+no_connect"))
    )
    (net (code "135") (name "unconnected-(J47-PadE13)") (class "Default")
      (node (ref "J47") (pin "E13") (pintype "passive+no_connect"))
    )
    (net (code "136") (name "unconnected-(J47-PadE15)") (class "Default")
      (node (ref "J47") (pin "E15") (pintype "passive+no_connect"))
    )
    (net (code "137") (name "unconnected-(J47-PadE16)") (class "Default")
      (node (ref "J47") (pin "E16") (pintype "passive+no_connect"))
    )
    (net (code "138") (name "unconnected-(J47-PadE18)") (class "Default")
      (node (ref "J47") (pin "E18") (pintype "passive+no_connect"))
    )
    (net (code "139") (name "unconnected-(J47-PadE19)") (class "Default")
      (node (ref "J47") (pin "E19") (pintype "passive+no_connect"))
    )
    (net (code "140") (name "unconnected-(J47-PadE21)") (class "Default")
      (node (ref "J47") (pin "E21") (pintype "passive+no_connect"))
    )
    (net (code "141") (name "unconnected-(J47-PadE22)") (class "Default")
      (node (ref "J47") (pin "E22") (pintype "passive+no_connect"))
    )
    (net (code "142") (name "unconnected-(J47-PadE24)") (class "Default")
      (node (ref "J47") (pin "E24") (pintype "passive+no_connect"))
    )
    (net (code "143") (name "unconnected-(J47-PadE25)") (class "Default")
      (node (ref "J47") (pin "E25") (pintype "passive+no_connect"))
    )
    (net (code "144") (name "unconnected-(J47-PadE27)") (class "Default")
      (node (ref "J47") (pin "E27") (pintype "passive+no_connect"))
    )
    (net (code "145") (name "unconnected-(J47-PadE28)") (class "Default")
      (node (ref "J47") (pin "E28") (pintype "passive+no_connect"))
    )
    (net (code "146") (name "unconnected-(J47-PadE30)") (class "Default")
      (node (ref "J47") (pin "E30") (pintype "passive+no_connect"))
    )
    (net (code "147") (name "unconnected-(J47-PadE31)") (class "Default")
      (node (ref "J47") (pin "E31") (pintype "passive+no_connect"))
    )
    (net (code "148") (name "unconnected-(J47-PadE33)") (class "Default")
      (node (ref "J47") (pin "E33") (pintype "passive+no_connect"))
    )
    (net (code "149") (name "unconnected-(J47-PadE34)") (class "Default")
      (node (ref "J47") (pin "E34") (pintype "passive+no_connect"))
    )
    (net (code "150") (name "unconnected-(J47-PadE36)") (class "Default")
      (node (ref "J47") (pin "E36") (pintype "passive+no_connect"))
    )
    (net (code "151") (name "unconnected-(J47-PadE37)") (class "Default")
      (node (ref "J47") (pin "E37") (pintype "passive+no_connect"))
    )
    (net (code "152") (name "unconnected-(J47-PadE39)") (class "Default")
      (node (ref "J47") (pin "E39") (pintype "passive+no_connect"))
    )
    (net (code "153") (name "unconnected-(J47-PadF1)") (class "Default")
      (node (ref "J47") (pin "F1") (pintype "passive+no_connect"))
    )
    (net (code "154") (name "unconnected-(J47-PadF4)") (class "Default")
      (node (ref "J47") (pin "F4") (pintype "passive+no_connect"))
    )
    (net (code "155") (name "unconnected-(J47-PadF5)") (class "Default")
      (node (ref "J47") (pin "F5") (pintype "passive+no_connect"))
    )
    (net (code "156") (name "unconnected-(J47-PadF7)") (class "Default")
      (node (ref "J47") (pin "F7") (pintype "passive+no_connect"))
    )
    (net (code "157") (name "unconnected-(J47-PadF8)") (class "Default")
      (node (ref "J47") (pin "F8") (pintype "passive+no_connect"))
    )
    (net (code "158") (name "unconnected-(J47-PadF10)") (class "Default")
      (node (ref "J47") (pin "F10") (pintype "passive+no_connect"))
    )
    (net (code "159") (name "unconnected-(J47-PadF11)") (class "Default")
      (node (ref "J47") (pin "F11") (pintype "passive+no_connect"))
    )
    (net (code "160") (name "unconnected-(J47-PadF13)") (class "Default")
      (node (ref "J47") (pin "F13") (pintype "passive+no_connect"))
    )
    (net (code "161") (name "unconnected-(J47-PadF14)") (class "Default")
      (node (ref "J47") (pin "F14") (pintype "passive+no_connect"))
    )
    (net (code "162") (name "unconnected-(J47-PadF16)") (class "Default")
      (node (ref "J47") (pin "F16") (pintype "passive+no_connect"))
    )
    (net (code "163") (name "unconnected-(J47-PadF17)") (class "Default")
      (node (ref "J47") (pin "F17") (pintype "passive+no_connect"))
    )
    (net (code "164") (name "unconnected-(J47-PadF19)") (class "Default")
      (node (ref "J47") (pin "F19") (pintype "passive+no_connect"))
    )
    (net (code "165") (name "unconnected-(J47-PadF20)") (class "Default")
      (node (ref "J47") (pin "F20") (pintype "passive+no_connect"))
    )
    (net (code "166") (name "unconnected-(J47-PadF22)") (class "Default")
      (node (ref "J47") (pin "F22") (pintype "passive+no_connect"))
    )
    (net (code "167") (name "unconnected-(J47-PadF23)") (class "Default")
      (node (ref "J47") (pin "F23") (pintype "passive+no_connect"))
    )
    (net (code "168") (name "unconnected-(J47-PadF25)") (class "Default")
      (node (ref "J47") (pin "F25") (pintype "passive+no_connect"))
    )
    (net (code "169") (name "unconnected-(J47-PadF26)") (class "Default")
      (node (ref "J47") (pin "F26") (pintype "passive+no_connect"))
    )
    (net (code "170") (name "unconnected-(J47-PadF28)") (class "Default")
      (node (ref "J47") (pin "F28") (pintype "passive+no_connect"))
    )
    (net (code "171") (name "unconnected-(J47-PadF29)") (class "Default")
      (node (ref "J47") (pin "F29") (pintype "passive+no_connect"))
    )
    (net (code "172") (name "unconnected-(J47-PadF31)") (class "Default")
      (node (ref "J47") (pin "F31") (pintype "passive+no_connect"))
    )
    (net (code "173") (name "unconnected-(J47-PadF32)") (class "Default")
      (node (ref "J47") (pin "F32") (pintype "passive+no_connect"))
    )
    (net (code "174") (name "unconnected-(J47-PadF34)") (class "Default")
      (node (ref "J47") (pin "F34") (pintype "passive+no_connect"))
    )
    (net (code "175") (name "unconnected-(J47-PadF35)") (class "Default")
      (node (ref "J47") (pin "F35") (pintype "passive+no_connect"))
    )
    (net (code "176") (name "unconnected-(J47-PadF37)") (class "Default")
      (node (ref "J47") (pin "F37") (pintype "passive+no_connect"))
    )
    (net (code "177") (name "unconnected-(J47-PadF38)") (class "Default")
      (node (ref "J47") (pin "F38") (pintype "passive+no_connect"))
    )
    (net (code "178") (name "unconnected-(J47-PadF40)") (class "Default")
      (node (ref "J47") (pin "F40") (pintype "passive+no_connect"))
    )
    (net (code "179") (name "unconnected-(J47-PadG2)") (class "Default")
      (node (ref "J47") (pin "G2") (pintype "passive+no_connect"))
    )
    (net (code "180") (name "unconnected-(J47-PadG3)") (class "Default")
      (node (ref "J47") (pin "G3") (pintype "passive+no_connect"))
    )
    (net (code "181") (name "unconnected-(J47-PadG18)") (class "Default")
      (node (ref "J47") (pin "G18") (pintype "passive+no_connect"))
    )
    (net (code "182") (name "unconnected-(J47-PadG19)") (class "Default")
      (node (ref "J47") (pin "G19") (pintype "passive+no_connect"))
    )
    (net (code "183") (name "unconnected-(J47-PadG21)") (class "Default")
      (node (ref "J47") (pin "G21") (pintype "passive+no_connect"))
    )
    (net (code "184") (name "unconnected-(J47-PadG22)") (class "Default")
      (node (ref "J47") (pin "G22") (pintype "passive+no_connect"))
    )
    (net (code "185") (name "unconnected-(J47-PadG24)") (class "Default")
      (node (ref "J47") (pin "G24") (pintype "passive+no_connect"))
    )
    (net (code "186") (name "unconnected-(J47-PadG25)") (class "Default")
      (node (ref "J47") (pin "G25") (pintype "passive+no_connect"))
    )
    (net (code "187") (name "unconnected-(J47-PadG27)") (class "Default")
      (node (ref "J47") (pin "G27") (pintype "passive+no_connect"))
    )
    (net (code "188") (name "unconnected-(J47-PadG28)") (class "Default")
      (node (ref "J47") (pin "G28") (pintype "passive+no_connect"))
    )
    (net (code "189") (name "unconnected-(J47-PadG30)") (class "Default")
      (node (ref "J47") (pin "G30") (pintype "passive+no_connect"))
    )
    (net (code "190") (name "unconnected-(J47-PadG31)") (class "Default")
      (node (ref "J47") (pin "G31") (pintype "passive+no_connect"))
    )
    (net (code "191") (name "unconnected-(J47-PadG33)") (class "Default")
      (node (ref "J47") (pin "G33") (pintype "passive+no_connect"))
    )
    (net (code "192") (name "unconnected-(J47-PadG34)") (class "Default")
      (node (ref "J47") (pin "G34") (pintype "passive+no_connect"))
    )
    (net (code "193") (name "unconnected-(J47-PadG36)") (class "Default")
      (node (ref "J47") (pin "G36") (pintype "passive+no_connect"))
    )
    (net (code "194") (name "unconnected-(J47-PadG37)") (class "Default")
      (node (ref "J47") (pin "G37") (pintype "passive+no_connect"))
    )
    (net (code "195") (name "unconnected-(J47-PadG39)") (class "Default")
      (node (ref "J47") (pin "G39") (pintype "passive+no_connect"))
    )
    (net (code "196") (name "unconnected-(J47-PadH1)") (class "Default")
      (node (ref "J47") (pin "H1") (pintype "passive+no_connect"))
    )
    (net (code "197") (name "unconnected-(J47-PadH4)") (class "Default")
      (node (ref "J47") (pin "H4") (pintype "passive+no_connect"))
    )
    (net (code "198") (name "unconnected-(J47-PadH5)") (class "Default")
      (node (ref "J47") (pin "H5") (pintype "passive+no_connect"))
    )
    (net (code "199") (name "unconnected-(J47-PadH7)") (class "Default")
      (node (ref "J47") (pin "H7") (pintype "passive+no_connect"))
    )
    (net (code "200") (name "unconnected-(J47-PadH8)") (class "Default")
      (node (ref "J47") (pin "H8") (pintype "passive+no_connect"))
    )
    (net (code "201") (name "unconnected-(J47-PadH10)") (class "Default")
      (node (ref "J47") (pin "H10") (pintype "passive+no_connect"))
    )
    (net (code "202") (name "unconnected-(J47-PadH11)") (class "Default")
      (node (ref "J47") (pin "H11") (pintype "passive+no_connect"))
    )
    (net (code "203") (name "unconnected-(J47-PadH13)") (class "Default")
      (node (ref "J47") (pin "H13") (pintype "passive+no_connect"))
    )
    (net (code "204") (name "unconnected-(J47-PadH14)") (class "Default")
      (node (ref "J47") (pin "H14") (pintype "passive+no_connect"))
    )
    (net (code "205") (name "unconnected-(J47-PadH19)") (class "Default")
      (node (ref "J47") (pin "H19") (pintype "passive+no_connect"))
    )
    (net (code "206") (name "unconnected-(J47-PadH20)") (class "Default")
      (node (ref "J47") (pin "H20") (pintype "passive+no_connect"))
    )
    (net (code "207") (name "unconnected-(J47-PadH22)") (class "Default")
      (node (ref "J47") (pin "H22") (pintype "passive+no_connect"))
    )
    (net (code "208") (name "unconnected-(J47-PadH23)") (class "Default")
      (node (ref "J47") (pin "H23") (pintype "passive+no_connect"))
    )
    (net (code "209") (name "unconnected-(J47-PadH25)") (class "Default")
      (node (ref "J47") (pin "H25") (pintype "passive+no_connect"))
    )
    (net (code "210") (name "unconnected-(J47-PadH26)") (class "Default")
      (node (ref "J47") (pin "H26") (pintype "passive+no_connect"))
    )
    (net (code "211") (name "unconnected-(J47-PadH28)") (class "Default")
      (node (ref "J47") (pin "H28") (pintype "passive+no_connect"))
    )
    (net (code "212") (name "unconnected-(J47-PadH29)") (class "Default")
      (node (ref "J47") (pin "H29") (pintype "passive+no_connect"))
    )
    (net (code "213") (name "unconnected-(J47-PadH31)") (class "Default")
      (node (ref "J47") (pin "H31") (pintype "passive+no_connect"))
    )
    (net (code "214") (name "unconnected-(J47-PadH32)") (class "Default")
      (node (ref "J47") (pin "H32") (pintype "passive+no_connect"))
    )
    (net (code "215") (name "unconnected-(J47-PadH34)") (class "Default")
      (node (ref "J47") (pin "H34") (pintype "passive+no_connect"))
    )
    (net (code "216") (name "unconnected-(J47-PadH35)") (class "Default")
      (node (ref "J47") (pin "H35") (pintype "passive+no_connect"))
    )
    (net (code "217") (name "unconnected-(J47-PadH37)") (class "Default")
      (node (ref "J47") (pin "H37") (pintype "passive+no_connect"))
    )
    (net (code "218") (name "unconnected-(J47-PadH38)") (class "Default")
      (node (ref "J47") (pin "H38") (pintype "passive+no_connect"))
    )
    (net (code "219") (name "unconnected-(J47-PadH40)") (class "Default")
      (node (ref "J47") (pin "H40") (pintype "passive+no_connect"))
    )
    (net (code "220") (name "unconnected-(J47-PadJ6)") (class "Default")
      (node (ref "J47") (pin "J6") (pintype "passive+no_connect"))
    )
    (net (code "221") (name "unconnected-(J47-PadJ7)") (class "Default")
      (node (ref "J47") (pin "J7") (pintype "passive+no_connect"))
    )
    (net (code "222") (name "unconnected-(J47-PadJ9)") (class "Default")
      (node (ref "J47") (pin "J9") (pintype "passive+no_connect"))
    )
    (net (code "223") (name "unconnected-(J47-PadJ10)") (class "Default")
      (node (ref "J47") (pin "J10") (pintype "passive+no_connect"))
    )
    (net (code "224") (name "unconnected-(J47-PadJ12)") (class "Default")
      (node (ref "J47") (pin "J12") (pintype "passive+no_connect"))
    )
    (net (code "225") (name "unconnected-(J47-PadJ13)") (class "Default")
      (node (ref "J47") (pin "J13") (pintype "passive+no_connect"))
    )
    (net (code "226") (name "unconnected-(J47-PadJ15)") (class "Default")
      (node (ref "J47") (pin "J15") (pintype "passive+no_connect"))
    )
    (net (code "227") (name "unconnected-(J47-PadJ16)") (class "Default")
      (node (ref "J47") (pin "J16") (pintype "passive+no_connect"))
    )
    (net (code "228") (name "unconnected-(J47-PadJ18)") (class "Default")
      (node (ref "J47") (pin "J18") (pintype "passive+no_connect"))
    )
    (net (code "229") (name "unconnected-(J47-PadJ19)") (class "Default")
      (node (ref "J47") (pin "J19") (pintype "passive+no_connect"))
    )
    (net (code "230") (name "unconnected-(J47-PadJ21)") (class "Default")
      (node (ref "J47") (pin "J21") (pintype "passive+no_connect"))
    )
    (net (code "231") (name "unconnected-(J47-PadJ22)") (class "Default")
      (node (ref "J47") (pin "J22") (pintype "passive+no_connect"))
    )
    (net (code "232") (name "unconnected-(J47-PadJ24)") (class "Default")
      (node (ref "J47") (pin "J24") (pintype "passive+no_connect"))
    )
    (net (code "233") (name "unconnected-(J47-PadJ25)") (class "Default")
      (node (ref "J47") (pin "J25") (pintype "passive+no_connect"))
    )
    (net (code "234") (name "unconnected-(J47-PadJ27)") (class "Default")
      (node (ref "J47") (pin "J27") (pintype "passive+no_connect"))
    )
    (net (code "235") (name "unconnected-(J47-PadJ28)") (class "Default")
      (node (ref "J47") (pin "J28") (pintype "passive+no_connect"))
    )
    (net (code "236") (name "unconnected-(J47-PadJ30)") (class "Default")
      (node (ref "J47") (pin "J30") (pintype "passive+no_connect"))
    )
    (net (code "237") (name "unconnected-(J47-PadJ31)") (class "Default")
      (node (ref "J47") (pin "J31") (pintype "passive+no_connect"))
    )
    (net (code "238") (name "unconnected-(J47-PadJ33)") (class "Default")
      (node (ref "J47") (pin "J33") (pintype "passive+no_connect"))
    )
    (net (code "239") (name "unconnected-(J47-PadJ34)") (class "Default")
      (node (ref "J47") (pin "J34") (pintype "passive+no_connect"))
    )
    (net (code "240") (name "unconnected-(J47-PadJ36)") (class "Default")
      (node (ref "J47") (pin "J36") (pintype "passive+no_connect"))
    )
    (net (code "241") (name "unconnected-(J47-PadJ37)") (class "Default")
      (node (ref "J47") (pin "J37") (pintype "passive+no_connect"))
    )
    (net (code "242") (name "unconnected-(J47-PadJ39)") (class "Default")
      (node (ref "J47") (pin "J39") (pintype "passive+no_connect"))
    )
    (net (code "243") (name "unconnected-(J47-PadK1)") (class "Default")
      (node (ref "J47") (pin "K1") (pintype "passive+no_connect"))
    )
    (net (code "244") (name "unconnected-(J47-PadK7)") (class "Default")
      (node (ref "J47") (pin "K7") (pintype "passive+no_connect"))
    )
    (net (code "245") (name "unconnected-(J47-PadK8)") (class "Default")
      (node (ref "J47") (pin "K8") (pintype "passive+no_connect"))
    )
    (net (code "246") (name "unconnected-(J47-PadK10)") (class "Default")
      (node (ref "J47") (pin "K10") (pintype "passive+no_connect"))
    )
    (net (code "247") (name "unconnected-(J47-PadK11)") (class "Default")
      (node (ref "J47") (pin "K11") (pintype "passive+no_connect"))
    )
    (net (code "248") (name "unconnected-(J47-PadK13)") (class "Default")
      (node (ref "J47") (pin "K13") (pintype "passive+no_connect"))
    )
    (net (code "249") (name "unconnected-(J47-PadK14)") (class "Default")
      (node (ref "J47") (pin "K14") (pintype "passive+no_connect"))
    )
    (net (code "250") (name "unconnected-(J47-PadK16)") (class "Default")
      (node (ref "J47") (pin "K16") (pintype "passive+no_connect"))
    )
    (net (code "251") (name "unconnected-(J47-PadK17)") (class "Default")
      (node (ref "J47") (pin "K17") (pintype "passive+no_connect"))
    )
    (net (code "252") (name "unconnected-(J47-PadK19)") (class "Default")
      (node (ref "J47") (pin "K19") (pintype "passive+no_connect"))
    )
    (net (code "253") (name "unconnected-(J47-PadK20)") (class "Default")
      (node (ref "J47") (pin "K20") (pintype "passive+no_connect"))
    )
    (net (code "254") (name "unconnected-(J47-PadK23)") (class "Default")
      (node (ref "J47") (pin "K23") (pintype "passive+no_connect"))
    )
    (net (code "255") (name "unconnected-(J47-PadK25)") (class "Default")
      (node (ref "J47") (pin "K25") (pintype "passive+no_connect"))
    )
    (net (code "256") (name "unconnected-(J47-PadK26)") (class "Default")
      (node (ref "J47") (pin "K26") (pintype "passive+no_connect"))
    )
    (net (code "257") (name "unconnected-(J47-PadK28)") (class "Default")
      (node (ref "J47") (pin "K28") (pintype "passive+no_connect"))
    )
    (net (code "258") (name "unconnected-(J47-PadK29)") (class "Default")
      (node (ref "J47") (pin "K29") (pintype "passive+no_connect"))
    )
    (net (code "259") (name "unconnected-(J47-PadK31)") (class "Default")
      (node (ref "J47") (pin "K31") (pintype "passive+no_connect"))
    )
    (net (code "260") (name "unconnected-(J47-PadK32)") (class "Default")
      (node (ref "J47") (pin "K32") (pintype "passive+no_connect"))
    )
    (net (code "261") (name "unconnected-(J47-PadK34)") (class "Default")
      (node (ref "J47") (pin "K34") (pintype "passive+no_connect"))
    )
    (net (code "262") (name "unconnected-(J47-PadK35)") (class "Default")
      (node (ref "J47") (pin "K35") (pintype "passive+no_connect"))
    )
    (net (code "263") (name "unconnected-(J47-PadK37)") (class "Default")
      (node (ref "J47") (pin "K37") (pintype "passive+no_connect"))
    )
    (net (code "264") (name "unconnected-(J47-PadK38)") (class "Default")
      (node (ref "J47") (pin "K38") (pintype "passive+no_connect"))
    )
    (net (code "265") (name "unconnected-(J47-PadK40)") (class "Default")
      (node (ref "J47") (pin "K40") (pintype "passive+no_connect"))
    )
    (net (code "266") (name "unconnected-(U3-NC-Pad7)") (class "Default")
      (node (ref "U3") (pin "7") (pinfunction "NC_7") (pintype "passive+no_connect"))
    )
  )
)
